# SW6124_A_A_B_C_Lighting_MCU_LED.net
KiCad netlist of a schematic drawn in Altium Designer
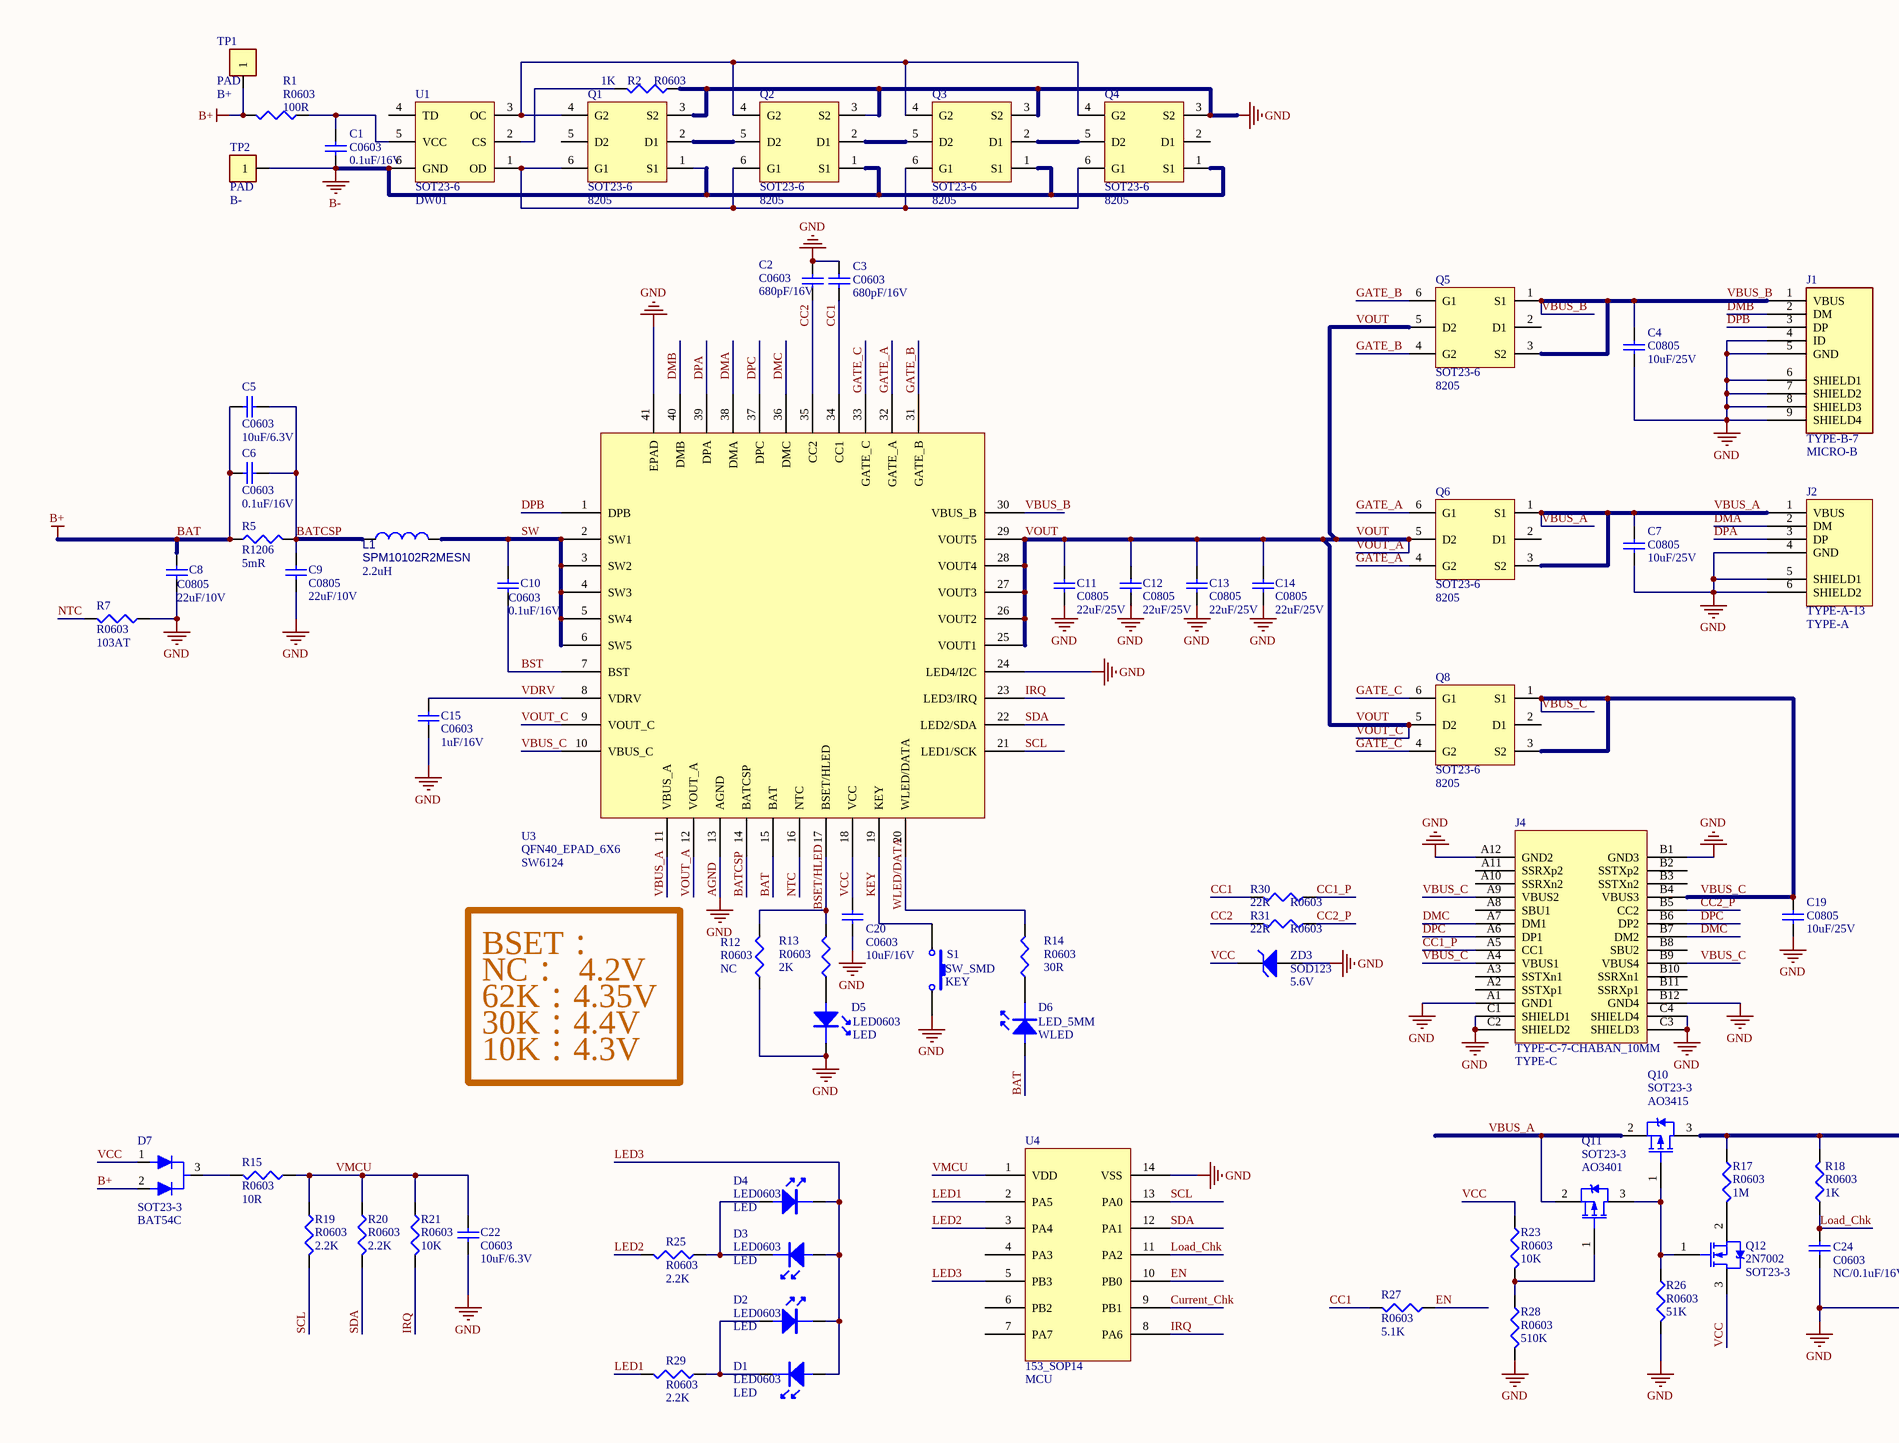
[diagram p0: SW6124+A+A+B+C+Lighting+MCU+LED.SchDoc, left]
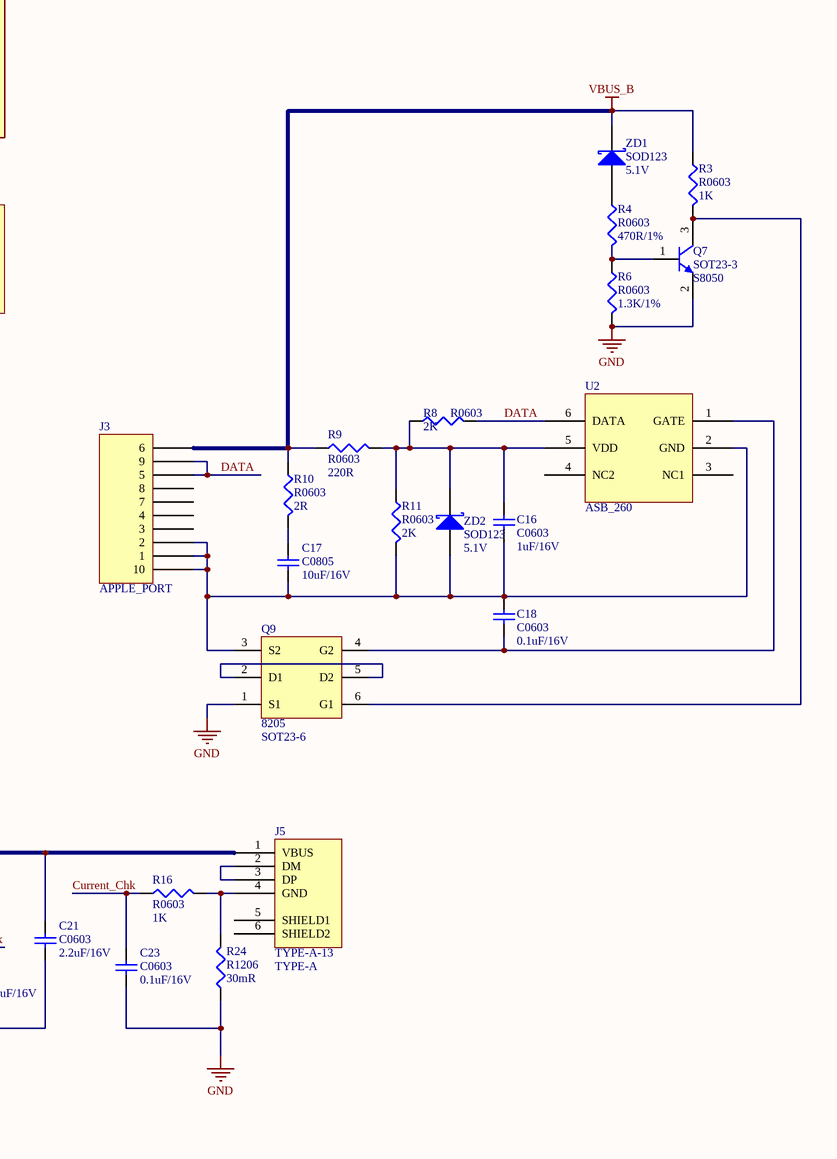
[diagram p1: SW6124+A+A+B+C+Lighting+MCU+LED.SchDoc, right]

(export (version "E")
  (design (tool "Eeschema 10.0.6"))
  (components
    (comp (ref "C1")
      (value "C0603")
      (footprint "C0603")
      (description "Capacitor")
      (fields (field (name "ALTIUM_VALUE") "0.1uF/16V") (field (name "PUBLISHER") "Altium Limited"))
      (libsource (lib "*") (part "Cap"))
    )
    (comp (ref "C2")
      (value "C0603")
      (footprint "C0603")
      (description "Capacitor")
      (fields (field (name "ALTIUM_VALUE") "680pF/16V") (field (name "PUBLISHER") "Altium Limited"))
      (libsource (lib "*") (part "CAP0603"))
    )
    (comp (ref "C3")
      (value "C0603")
      (footprint "C0603")
      (description "Capacitor")
      (fields (field (name "ALTIUM_VALUE") "680pF/16V") (field (name "PUBLISHER") "Altium Limited"))
      (libsource (lib "*") (part "CAP0603"))
    )
    (comp (ref "C4")
      (value "C0805")
      (footprint "C0805")
      (description "Capacitor")
      (fields (field (name "ALTIUM_VALUE") "10uF/25V") (field (name "PUBLISHER") "Altium Limited"))
      (libsource (lib "*") (part "CAP0603"))
    )
    (comp (ref "C5")
      (value "C0603")
      (footprint "C0603")
      (description "Capacitor")
      (fields (field (name "ALTIUM_VALUE") "10uF/6.3V") (field (name "PUBLISHER") "Altium Limited"))
      (libsource (lib "*") (part "CAP0603"))
    )
    (comp (ref "C6")
      (value "C0603")
      (footprint "C0603")
      (description "Capacitor")
      (fields (field (name "ALTIUM_VALUE") "0.1uF/16V") (field (name "PUBLISHER") "Altium Limited"))
      (libsource (lib "*") (part "CAP0603"))
    )
    (comp (ref "C7")
      (value "C0805")
      (footprint "C0805")
      (description "Capacitor")
      (fields (field (name "ALTIUM_VALUE") "10uF/25V") (field (name "PUBLISHER") "Altium Limited"))
      (libsource (lib "*") (part "CAP0603"))
    )
    (comp (ref "C8")
      (value "C0805")
      (footprint "C0805")
      (description "Capacitor")
      (fields (field (name "ALTIUM_VALUE") "22uF/10V") (field (name "PUBLISHER") "Altium Limited"))
      (libsource (lib "*") (part "CAP0805"))
    )
    (comp (ref "C9")
      (value "C0805")
      (footprint "C0805")
      (description "Capacitor")
      (fields (field (name "ALTIUM_VALUE") "22uF/10V") (field (name "PUBLISHER") "Altium Limited"))
      (libsource (lib "*") (part "CAP0805"))
    )
    (comp (ref "C10")
      (value "C0603")
      (footprint "C0603")
      (description "Capacitor")
      (fields (field (name "ALTIUM_VALUE") "0.1uF/16V") (field (name "PUBLISHER") "Altium Limited"))
      (libsource (lib "*") (part "CAP0603"))
    )
    (comp (ref "C11")
      (value "C0805")
      (footprint "C0805")
      (description "Capacitor")
      (fields (field (name "ALTIUM_VALUE") "22uF/25V") (field (name "PUBLISHER") "Altium Limited"))
      (libsource (lib "*") (part "CAP0805"))
    )
    (comp (ref "C12")
      (value "C0805")
      (footprint "C0805")
      (description "Capacitor")
      (fields (field (name "ALTIUM_VALUE") "22uF/25V") (field (name "PUBLISHER") "Altium Limited"))
      (libsource (lib "*") (part "CAP0805"))
    )
    (comp (ref "C13")
      (value "C0805")
      (footprint "C0805")
      (description "Capacitor")
      (fields (field (name "ALTIUM_VALUE") "22uF/25V") (field (name "PUBLISHER") "Altium Limited"))
      (libsource (lib "*") (part "CAP0805"))
    )
    (comp (ref "C14")
      (value "C0805")
      (footprint "C0805")
      (description "Capacitor")
      (fields (field (name "ALTIUM_VALUE") "22uF/25V") (field (name "PUBLISHER") "Altium Limited"))
      (libsource (lib "*") (part "CAP0805"))
    )
    (comp (ref "C15")
      (value "C0603")
      (footprint "C0603")
      (description "Capacitor")
      (fields (field (name "ALTIUM_VALUE") "1uF/16V") (field (name "PUBLISHER") "Altium Limited"))
      (libsource (lib "*") (part "CAP0603"))
    )
    (comp (ref "C16")
      (value "C0603")
      (footprint "C0603")
      (description "Capacitor")
      (fields (field (name "ALTIUM_VALUE") "1uF/16V") (field (name "PUBLISHER") "Altium Limited"))
      (libsource (lib "*") (part "CAP0805"))
    )
    (comp (ref "C17")
      (value "C0805")
      (footprint "C0805")
      (description "Capacitor")
      (fields (field (name "ALTIUM_VALUE") "10uF/16V") (field (name "PUBLISHER") "Altium Limited"))
      (libsource (lib "*") (part "CAP0805"))
    )
    (comp (ref "C18")
      (value "C0603")
      (footprint "C0603")
      (description "Capacitor")
      (fields (field (name "ALTIUM_VALUE") "0.1uF/16V") (field (name "PUBLISHER") "Altium Limited"))
      (libsource (lib "*") (part "CAP0805"))
    )
    (comp (ref "C19")
      (value "C0805")
      (footprint "C0805")
      (description "Capacitor")
      (fields (field (name "ALTIUM_VALUE") "10uF/25V") (field (name "PUBLISHER") "Altium Limited"))
      (libsource (lib "*") (part "CAP0603"))
    )
    (comp (ref "C20")
      (value "C0603")
      (footprint "C0603")
      (description "Capacitor")
      (fields (field (name "ALTIUM_VALUE") "10uF/16V") (field (name "PUBLISHER") "Altium Limited"))
      (libsource (lib "*") (part "CAP0603"))
    )
    (comp (ref "C21")
      (value "C0603")
      (footprint "C0603")
      (description "Capacitor")
      (fields (field (name "ALTIUM_VALUE") "2.2uF/16V") (field (name "PUBLISHER") "Altium Limited"))
      (libsource (lib "*") (part "CAP0603"))
    )
    (comp (ref "C22")
      (value "C0603")
      (footprint "C0603")
      (description "Capacitor")
      (fields (field (name "ALTIUM_VALUE") "10uF/6.3V") (field (name "PUBLISHER") "Altium Limited"))
      (libsource (lib "*") (part "CAP0603"))
    )
    (comp (ref "C23")
      (value "C0603")
      (footprint "C0603")
      (description "Capacitor")
      (fields (field (name "ALTIUM_VALUE") "0.1uF/16V") (field (name "PUBLISHER") "Altium Limited"))
      (libsource (lib "*") (part "CAP0603"))
    )
    (comp (ref "C24")
      (value "C0603")
      (footprint "C0603")
      (description "Capacitor")
      (fields (field (name "ALTIUM_VALUE") "NC/0.1uF/16V") (field (name "PUBLISHER") "Altium Limited"))
      (libsource (lib "*") (part "CAP0603"))
    )
    (comp (ref "D1") (value "LED") (footprint "LED0603") (libsource (lib "*") (part "LED")))
    (comp (ref "D2") (value "LED") (footprint "LED0603") (libsource (lib "*") (part "LED")))
    (comp (ref "D3") (value "LED") (footprint "LED0603") (libsource (lib "*") (part "LED")))
    (comp (ref "D4") (value "LED") (footprint "LED0603") (libsource (lib "*") (part "LED")))
    (comp (ref "D5") (value "LED") (footprint "LED0603") (libsource (lib "*") (part "LED")))
    (comp (ref "D6")
      (value "WLED")
      (footprint "LED_5MM")
      (fields (field (name "FOOTPRINF") "LED_5MM") (field (name "Comment") "LED_5MM"))
      (libsource (lib "*") (part "LED"))
    )
    (comp (ref "D7") (value "BAT54C") (footprint "SOT23-3") (libsource (lib "Schlib1-2012") (part "D3")))
    (comp (ref "J1")
      (value "MICRO-B")
      (footprint "TYPE-B-7")
      (fields (field (name "FOOTPRINTF") "TYPE-B-7") (field (name "Comment") "USB_MICRO_B"))
      (libsource (lib "*") (part "USB_MICRO_B"))
    )
    (comp (ref "J2")
      (value "TYPE-A")
      (footprint "TYPE-A-13")
      (fields (field (name "FOOTPRINF") "TYPE-A-13") (field (name "Comment") "TYPE-A-1"))
      (libsource (lib "*") (part "TYPE-A-1"))
    )
    (comp (ref "J3") (value "APPLE_PORT") (libsource (lib "TEST") (part "APPLE_PORT")))
    (comp (ref "J4")
      (value "TYPE-C")
      (footprint "TYPE-C-7-CHABAN_10MM")
      (libsource (lib "*") (part "TYPE-C"))
    )
    (comp (ref "J5")
      (value "TYPE-A")
      (footprint "PIE10-USB")
      (fields (field (name "FOOTPRINF") "TYPE-A-13") (field (name "Comment") "TYPE-A-1"))
      (libsource (lib "*") (part "TYPE-A-1"))
    )
    (comp (ref "L1")
      (value "SPM10102R2MESN")
      (footprint "INDUCTOR_SPM1010")
      (fields (field (name "ALTIUM_VALUE") "2.2uH"))
      (libsource (lib "*") (part "INDUCTOR"))
    )
    (comp (ref "Q1")
      (value "8205")
      (footprint "SOT23-6")
      (fields (field (name "FOOTPRINF") "SOT23-6"))
      (libsource (lib "") (part "8205B_2"))
    )
    (comp (ref "Q2")
      (value "8205")
      (footprint "SOT23-6")
      (fields (field (name "FOOTPRINF") "SOT23-6"))
      (libsource (lib "") (part "8205B_2"))
    )
    (comp (ref "Q3")
      (value "8205")
      (footprint "SOT23-6")
      (fields (field (name "FOOTPRINF") "SOT23-6"))
      (libsource (lib "") (part "8205B_2"))
    )
    (comp (ref "Q4")
      (value "8205")
      (footprint "SOT23-6")
      (fields (field (name "FOOTPRINF") "SOT23-6"))
      (libsource (lib "") (part "8205B_2"))
    )
    (comp (ref "Q5")
      (value "8205")
      (footprint "SOT23-6")
      (fields (field (name "FOOTPRINF") "SOT23-6"))
      (libsource (lib "*") (part "8205B"))
    )
    (comp (ref "Q6")
      (value "8205")
      (footprint "SOT23-6")
      (fields (field (name "FOOTPRINF") "SOT23-6"))
      (libsource (lib "*") (part "8205B"))
    )
    (comp (ref "Q7")
      (value "S8050")
      (footprint "SOT23-3")
      (description "NPN General Purpose Amplifier")
      (fields (field (name "PUBLISHER") "Altium Limited"))
      (libsource (lib "Miscellaneous Devices") (part "2N3904"))
    )
    (comp (ref "Q8")
      (value "8205")
      (footprint "SOT23-6")
      (fields (field (name "FOOTPRINF") "SOT23-6"))
      (libsource (lib "*") (part "8205B"))
    )
    (comp (ref "Q9")
      (value "8205")
      (footprint "SOT23-6")
      (fields (field (name "FOOTPRINF") "SOT23-6"))
      (libsource (lib "") (part "8205B_1"))
    )
    (comp (ref "Q10")
      (value "AO3415")
      (footprint "SOT23-3")
      (description "P-Channel Power MOSFET")
      (fields (field (name "Comment") "PMOS-2") (field (name "PUBLISHER") "Altium Limited"))
      (libsource (lib "Miscellaneous Devices") (part "PMOS-2"))
    )
    (comp (ref "Q11")
      (value "AO3401")
      (footprint "SOT23-3")
      (description "P-Channel Power MOSFET")
      (fields (field (name "Comment") "PMOS-2") (field (name "PUBLISHER") "Altium Limited"))
      (libsource (lib "Miscellaneous Devices") (part "PMOS-2"))
    )
    (comp (ref "Q12")
      (value "2N7002")
      (footprint "SOT23-3")
      (description "N-Channel Power MOSFET")
      (fields (field (name "Comment") "NMOS-2") (field (name "PUBLISHER") "Altium Limited"))
      (libsource (lib "Miscellaneous Devices") (part "NMOS-2"))
    )
    (comp (ref "R1")
      (value "R0603")
      (footprint "R0603")
      (description "Resistor")
      (fields (field (name "ALTIUM_VALUE") "100R") (field (name "PUBLISHER") "Altium Limited"))
      (libsource (lib "*") (part "Res3"))
    )
    (comp (ref "R2")
      (value "R0603")
      (footprint "R0603")
      (description "Resistor")
      (fields (field (name "ALTIUM_VALUE") "1K") (field (name "PUBLISHER") "Altium Limited"))
      (libsource (lib "*") (part "Res3"))
    )
    (comp (ref "R3")
      (value "R0603")
      (footprint "R0603")
      (description "Resistor")
      (fields (field (name "ALTIUM_VALUE") "1K") (field (name "PUBLISHER") "Altium Limited"))
      (libsource (lib "Miscellaneous Devices") (part "Res3"))
    )
    (comp (ref "R4")
      (value "R0603")
      (footprint "R0603")
      (description "Resistor")
      (fields (field (name "ALTIUM_VALUE") "470R/1%") (field (name "PUBLISHER") "Altium Limited"))
      (libsource (lib "Miscellaneous Devices") (part "Res3"))
    )
    (comp (ref "R5")
      (value "R1206")
      (footprint "R1206")
      (description "Resistor")
      (fields (field (name "ALTIUM_VALUE") "5mR") (field (name "PUBLISHER") "Altium Limited"))
      (libsource (lib "*") (part "RES"))
    )
    (comp (ref "R6")
      (value "R0603")
      (footprint "R0603")
      (description "Resistor")
      (fields (field (name "ALTIUM_VALUE") "1.3K/1%") (field (name "PUBLISHER") "Altium Limited"))
      (libsource (lib "Miscellaneous Devices") (part "Res3"))
    )
    (comp (ref "R7")
      (value "R0603")
      (footprint "R0603")
      (description "Resistor")
      (fields (field (name "ALTIUM_VALUE") "103AT") (field (name "PUBLISHER") "Altium Limited"))
      (libsource (lib "*") (part "RES"))
    )
    (comp (ref "R8")
      (value "R0603")
      (footprint "R0603")
      (description "Resistor")
      (fields (field (name "ALTIUM_VALUE") "2K") (field (name "PUBLISHER") "Altium Limited"))
      (libsource (lib "Miscellaneous Devices") (part "Res3"))
    )
    (comp (ref "R9")
      (value "R0603")
      (footprint "R0603")
      (description "Resistor")
      (fields (field (name "ALTIUM_VALUE") "220R") (field (name "PUBLISHER") "Altium Limited"))
      (libsource (lib "Miscellaneous Devices") (part "Res3"))
    )
    (comp (ref "R10")
      (value "R0603")
      (footprint "R0603")
      (description "Resistor")
      (fields (field (name "ALTIUM_VALUE") "2R") (field (name "PUBLISHER") "Altium Limited"))
      (libsource (lib "Miscellaneous Devices") (part "Res3"))
    )
    (comp (ref "R11")
      (value "R0603")
      (footprint "R0603")
      (description "Resistor")
      (fields (field (name "ALTIUM_VALUE") "2K") (field (name "PUBLISHER") "Altium Limited"))
      (libsource (lib "Miscellaneous Devices") (part "Res3"))
    )
    (comp (ref "R12")
      (value "R0603")
      (footprint "R0603")
      (description "Resistor")
      (fields (field (name "ALTIUM_VALUE") "NC") (field (name "PUBLISHER") "Altium Limited"))
      (libsource (lib "*") (part "RES"))
    )
    (comp (ref "R13")
      (value "R0603")
      (footprint "R0603")
      (description "Resistor")
      (fields (field (name "ALTIUM_VALUE") "2K") (field (name "PUBLISHER") "Altium Limited"))
      (libsource (lib "*") (part "RES"))
    )
    (comp (ref "R14")
      (value "R0603")
      (footprint "R0603")
      (description "Resistor")
      (fields (field (name "ALTIUM_VALUE") "30R") (field (name "PUBLISHER") "Altium Limited"))
      (libsource (lib "*") (part "RES"))
    )
    (comp (ref "R15")
      (value "R0603")
      (footprint "R0603")
      (description "Resistor")
      (fields (field (name "ALTIUM_VALUE") "10R") (field (name "PUBLISHER") "Altium Limited"))
      (libsource (lib "*") (part "RES"))
    )
    (comp (ref "R16")
      (value "R0603")
      (footprint "R0603")
      (description "Resistor")
      (fields (field (name "ALTIUM_VALUE") "1K") (field (name "PUBLISHER") "Altium Limited"))
      (libsource (lib "*") (part "RES"))
    )
    (comp (ref "R17")
      (value "R0603")
      (footprint "R0603")
      (description "Resistor")
      (fields (field (name "ALTIUM_VALUE") "1M") (field (name "PUBLISHER") "Altium Limited"))
      (libsource (lib "*") (part "RES"))
    )
    (comp (ref "R18")
      (value "R0603")
      (footprint "R0603")
      (description "Resistor")
      (fields (field (name "ALTIUM_VALUE") "1K") (field (name "PUBLISHER") "Altium Limited"))
      (libsource (lib "*") (part "RES"))
    )
    (comp (ref "R19")
      (value "R0603")
      (footprint "R0603")
      (description "Resistor")
      (fields (field (name "ALTIUM_VALUE") "2.2K") (field (name "PUBLISHER") "Altium Limited"))
      (libsource (lib "*") (part "RES"))
    )
    (comp (ref "R20")
      (value "R0603")
      (footprint "R0603")
      (description "Resistor")
      (fields (field (name "ALTIUM_VALUE") "2.2K") (field (name "PUBLISHER") "Altium Limited"))
      (libsource (lib "*") (part "RES"))
    )
    (comp (ref "R21")
      (value "R0603")
      (footprint "R0603")
      (description "Resistor")
      (fields (field (name "ALTIUM_VALUE") "10K") (field (name "PUBLISHER") "Altium Limited"))
      (libsource (lib "*") (part "RES"))
    )
    (comp (ref "R23")
      (value "R0603")
      (footprint "R0603")
      (description "Resistor")
      (fields (field (name "ALTIUM_VALUE") "10K") (field (name "PUBLISHER") "Altium Limited"))
      (libsource (lib "*") (part "RES"))
    )
    (comp (ref "R24")
      (value "R1206")
      (footprint "C-1206A")
      (description "Resistor")
      (fields (field (name "ALTIUM_VALUE") "30mR") (field (name "PUBLISHER") "Altium Limited"))
      (libsource (lib "*") (part "RES"))
    )
    (comp (ref "R25")
      (value "R0603")
      (footprint "R0603")
      (description "Resistor")
      (fields (field (name "ALTIUM_VALUE") "2.2K") (field (name "PUBLISHER") "Altium Limited"))
      (libsource (lib "*") (part "RES"))
    )
    (comp (ref "R26")
      (value "R0603")
      (footprint "R0603")
      (description "Resistor")
      (fields (field (name "ALTIUM_VALUE") "51K") (field (name "PUBLISHER") "Altium Limited"))
      (libsource (lib "*") (part "RES"))
    )
    (comp (ref "R27")
      (value "R0603")
      (footprint "R0603")
      (description "Resistor")
      (fields (field (name "ALTIUM_VALUE") "5.1K") (field (name "PUBLISHER") "Altium Limited"))
      (libsource (lib "*") (part "RES"))
    )
    (comp (ref "R28")
      (value "R0603")
      (footprint "R0603")
      (description "Resistor")
      (fields (field (name "ALTIUM_VALUE") "510K") (field (name "PUBLISHER") "Altium Limited"))
      (libsource (lib "*") (part "RES"))
    )
    (comp (ref "R29")
      (value "R0603")
      (footprint "R0603")
      (description "Resistor")
      (fields (field (name "ALTIUM_VALUE") "2.2K") (field (name "PUBLISHER") "Altium Limited"))
      (libsource (lib "*") (part "RES"))
    )
    (comp (ref "R30")
      (value "R0603")
      (footprint "R0603")
      (description "Resistor")
      (fields (field (name "ALTIUM_VALUE") "22R") (field (name "PUBLISHER") "Altium Limited"))
      (libsource (lib "*") (part "RES"))
    )
    (comp (ref "R31")
      (value "R0603")
      (footprint "R0603")
      (description "Resistor")
      (fields (field (name "ALTIUM_VALUE") "22R") (field (name "PUBLISHER") "Altium Limited"))
      (libsource (lib "*") (part "RES"))
    )
    (comp (ref "S1")
      (value "KEY")
      (footprint "SW_SMD")
      (fields (field (name "FOOTPRINF") "SW_SMD"))
      (libsource (lib "*") (part "SW K"))
    )
    (comp (ref "TP1") (value "B+") (footprint "PAD") (libsource (lib "*") (part "Test Point")))
    (comp (ref "TP2") (value "B-") (footprint "PAD") (libsource (lib "") (part "Test Point_1")))
    (comp (ref "U1")
      (value "DW01")
      (footprint "SOT23-6")
      (fields (field (name "FOOTPRINF") "SOT23-6"))
      (libsource (lib "*") (part "DW01"))
    )
    (comp (ref "U2") (value "ASB_260") (footprint "SOT-23-") (libsource (lib "TEST") (part "ASB_260")))
    (comp (ref "U3")
      (value "SW6124")
      (footprint "QFN40_EPAD_6X6")
      (libsource (lib "TEST") (part "SW6106_AFC"))
    )
    (comp (ref "U4")
      (value "153_SOP14")
      (fields (field (name "ALTIUM_VALUE") "MCU"))
      (libsource (lib "TEST") (part "153_SOP14"))
    )
    (comp (ref "ZD1")
      (value "5.1V")
      (footprint "SOD123")
      (description "Schottky Rectifier")
      (fields (field (name "Comment") "SOD123") (field (name "PUBLISHER") "Altium Limited"))
      (libsource (lib "Miscellaneous Devices") (part "Diode 11DQ03"))
    )
    (comp (ref "ZD2")
      (value "5.1V")
      (footprint "SOD123")
      (description "Schottky Rectifier")
      (fields (field (name "Comment") "SOD123") (field (name "PUBLISHER") "Altium Limited"))
      (libsource (lib "Miscellaneous Devices") (part "Diode 11DQ03"))
    )
    (comp (ref "ZD3")
      (value "SOD123")
      (footprint "SOD-123")
      (description "Zener Diode")
      (fields (field (name "ALTIUM_VALUE") "5.6V"))
      (libsource (lib "Miscellaneous Devices") (part "D Zener"))
    )
  )
  (nets
    (net (code "1") (name "/BATCSP") (class "Default")
      (node (ref "C5") (pin "2") (pinfunction "2_2") (pintype "passive"))
      (node (ref "C6") (pin "2") (pinfunction "2_2") (pintype "passive"))
      (node (ref "C9") (pin "2") (pinfunction "2_2") (pintype "passive"))
      (node (ref "L1") (pin "1") (pinfunction "1_1") (pintype "passive"))
      (node (ref "R5") (pin "2") (pinfunction "2_2") (pintype "passive"))
      (node (ref "U3") (pin "14") (pinfunction "BATCSP_14") (pintype "passive"))
    )
    (net (code "2") (name "/BSET{slash}HLED") (class "Default")
      (node (ref "R12") (pin "2") (pinfunction "2_2") (pintype "passive"))
      (node (ref "R13") (pin "2") (pinfunction "2_2") (pintype "passive"))
      (node (ref "U3") (pin "17") (pinfunction "BSET/HLED_17") (pintype "passive"))
    )
    (net (code "3") (name "/BST") (class "Default")
      (node (ref "C10") (pin "1") (pinfunction "1_1") (pintype "passive"))
      (node (ref "U3") (pin "7") (pinfunction "BST_7") (pintype "passive"))
    )
    (net (code "4") (name "/CC1") (class "Default")
      (node (ref "C3") (pin "1") (pinfunction "1_1") (pintype "passive"))
      (node (ref "R27") (pin "2") (pinfunction "2_2") (pintype "passive"))
      (node (ref "R30") (pin "2") (pinfunction "2_2") (pintype "passive"))
      (node (ref "U3") (pin "34") (pinfunction "CC1_34") (pintype "passive"))
    )
    (net (code "5") (name "/CC1_P") (class "Default")
      (node (ref "J4") (pin "A5") (pinfunction "CC1_A5") (pintype "passive"))
      (node (ref "R30") (pin "1") (pinfunction "1_1") (pintype "passive"))
    )
    (net (code "6") (name "/CC2") (class "Default")
      (node (ref "C2") (pin "1") (pinfunction "1_1") (pintype "passive"))
      (node (ref "R31") (pin "2") (pinfunction "2_2") (pintype "passive"))
      (node (ref "U3") (pin "35") (pinfunction "CC2_35") (pintype "passive"))
    )
    (net (code "7") (name "/CC2_P") (class "Default")
      (node (ref "J4") (pin "B5") (pinfunction "CC2_B5") (pintype "passive"))
      (node (ref "R31") (pin "1") (pinfunction "1_1") (pintype "passive"))
    )
    (net (code "8") (name "/Current_Chk") (class "Default")
      (node (ref "C23") (pin "2") (pinfunction "2_2") (pintype "passive"))
      (node (ref "R16") (pin "1") (pinfunction "1_1") (pintype "passive"))
      (node (ref "U4") (pin "9") (pinfunction "PB1_9") (pintype "passive"))
    )
    (net (code "9") (name "/DATA") (class "Default")
      (node (ref "J3") (pin "5") (pinfunction "5_5") (pintype "passive"))
      (node (ref "J3") (pin "9") (pinfunction "9_9") (pintype "passive"))
      (node (ref "R8") (pin "2") (pinfunction "2_2") (pintype "passive"))
      (node (ref "U2") (pin "6") (pinfunction "DATA_6") (pintype "passive"))
    )
    (net (code "10") (name "/DMA") (class "Default")
      (node (ref "J2") (pin "2") (pinfunction "DM_2") (pintype "passive"))
      (node (ref "U3") (pin "38") (pinfunction "DMA_38") (pintype "passive"))
    )
    (net (code "11") (name "/DMB") (class "Default")
      (node (ref "J1") (pin "2") (pinfunction "DM_2") (pintype "passive"))
      (node (ref "U3") (pin "40") (pinfunction "DMB_40") (pintype "passive"))
    )
    (net (code "12") (name "/DMC") (class "Default")
      (node (ref "J4") (pin "A7") (pinfunction "DM1_A7") (pintype "passive"))
      (node (ref "J4") (pin "B7") (pinfunction "DM2_B7") (pintype "passive"))
      (node (ref "U3") (pin "36") (pinfunction "DMC_36") (pintype "passive"))
    )
    (net (code "13") (name "/DPA") (class "Default")
      (node (ref "J2") (pin "3") (pinfunction "DP_3") (pintype "passive"))
      (node (ref "U3") (pin "39") (pinfunction "DPA_39") (pintype "passive"))
    )
    (net (code "14") (name "/DPB") (class "Default")
      (node (ref "J1") (pin "3") (pinfunction "DP_3") (pintype "passive"))
      (node (ref "U3") (pin "1") (pinfunction "DPB_1") (pintype "passive"))
    )
    (net (code "15") (name "/DPC") (class "Default")
      (node (ref "J4") (pin "A6") (pinfunction "DP1_A6") (pintype "passive"))
      (node (ref "J4") (pin "B6") (pinfunction "DP2_B6") (pintype "passive"))
      (node (ref "U3") (pin "37") (pinfunction "DPC_37") (pintype "passive"))
    )
    (net (code "16") (name "/EN") (class "Default")
      (node (ref "R27") (pin "1") (pinfunction "1_1") (pintype "passive"))
      (node (ref "U4") (pin "10") (pinfunction "PB0_10") (pintype "passive"))
    )
    (net (code "17") (name "/GATE_A") (class "Default")
      (node (ref "Q6") (pin "4") (pinfunction "G2_4") (pintype "passive"))
      (node (ref "Q6") (pin "6") (pinfunction "G1_6") (pintype "passive"))
      (node (ref "U3") (pin "32") (pinfunction "GATE_A_32") (pintype "passive"))
    )
    (net (code "18") (name "/GATE_B") (class "Default")
      (node (ref "Q5") (pin "4") (pinfunction "G2_4") (pintype "passive"))
      (node (ref "Q5") (pin "6") (pinfunction "G1_6") (pintype "passive"))
      (node (ref "U3") (pin "31") (pinfunction "GATE_B_31") (pintype "passive"))
    )
    (net (code "19") (name "/GATE_C") (class "Default")
      (node (ref "Q8") (pin "4") (pinfunction "G2_4") (pintype "passive"))
      (node (ref "Q8") (pin "6") (pinfunction "G1_6") (pintype "passive"))
      (node (ref "U3") (pin "33") (pinfunction "GATE_C_33") (pintype "passive"))
    )
    (net (code "20") (name "/IRQ") (class "Default")
      (node (ref "R21") (pin "2") (pinfunction "2_2") (pintype "passive"))
      (node (ref "U3") (pin "23") (pinfunction "LED3/IRQ_23") (pintype "passive"))
      (node (ref "U4") (pin "8") (pinfunction "PA6_8") (pintype "passive"))
    )
    (net (code "21") (name "/KEY") (class "Default")
      (node (ref "S1") (pin "1") (pinfunction "1_1") (pintype "passive"))
      (node (ref "U3") (pin "19") (pinfunction "KEY_19") (pintype "passive"))
    )
    (net (code "22") (name "/LED1") (class "Default")
      (node (ref "R29") (pin "2") (pinfunction "2_2") (pintype "passive"))
      (node (ref "U4") (pin "2") (pinfunction "PA5_2") (pintype "passive"))
    )
    (net (code "23") (name "/LED2") (class "Default")
      (node (ref "R25") (pin "2") (pinfunction "2_2") (pintype "passive"))
      (node (ref "U4") (pin "3") (pinfunction "PA4_3") (pintype "passive"))
    )
    (net (code "24") (name "/LED3") (class "Default")
      (node (ref "D1") (pin "1") (pinfunction "A_1") (pintype "passive"))
      (node (ref "D2") (pin "2") (pinfunction "K_2") (pintype "passive"))
      (node (ref "D3") (pin "1") (pinfunction "A_1") (pintype "passive"))
      (node (ref "D4") (pin "2") (pinfunction "K_2") (pintype "passive"))
      (node (ref "U4") (pin "5") (pinfunction "PB3_5") (pintype "passive"))
    )
    (net (code "25") (name "/Load_Chk") (class "Default")
      (node (ref "C24") (pin "2") (pinfunction "2_2") (pintype "passive"))
      (node (ref "R18") (pin "1") (pinfunction "1_1") (pintype "passive"))
      (node (ref "U4") (pin "11") (pinfunction "PA2_11") (pintype "passive"))
    )
    (net (code "26") (name "/NTC") (class "Default")
      (node (ref "R7") (pin "2") (pinfunction "2_2") (pintype "passive"))
      (node (ref "U3") (pin "16") (pinfunction "NTC_16") (pintype "passive"))
    )
    (net (code "27") (name "/SCL") (class "Default")
      (node (ref "R19") (pin "2") (pinfunction "2_2") (pintype "passive"))
      (node (ref "U3") (pin "21") (pinfunction "LED1/SCK_21") (pintype "passive"))
      (node (ref "U4") (pin "13") (pinfunction "PA0_13") (pintype "passive"))
    )
    (net (code "28") (name "/SDA") (class "Default")
      (node (ref "R20") (pin "2") (pinfunction "2_2") (pintype "passive"))
      (node (ref "U3") (pin "22") (pinfunction "LED2/SDA_22") (pintype "passive"))
      (node (ref "U4") (pin "12") (pinfunction "PA1_12") (pintype "passive"))
    )
    (net (code "29") (name "/SW") (class "Default")
      (node (ref "C10") (pin "2") (pinfunction "2_2") (pintype "passive"))
      (node (ref "L1") (pin "2") (pinfunction "2_2") (pintype "passive"))
      (node (ref "U3") (pin "2") (pinfunction "SW1_2") (pintype "passive"))
      (node (ref "U3") (pin "3") (pinfunction "SW2_3") (pintype "passive"))
      (node (ref "U3") (pin "4") (pinfunction "SW3_4") (pintype "passive"))
      (node (ref "U3") (pin "5") (pinfunction "SW4_5") (pintype "passive"))
      (node (ref "U3") (pin "6") (pinfunction "SW5_6") (pintype "passive"))
    )
    (net (code "30") (name "/VBUS_A") (class "Default")
      (node (ref "C7") (pin "2") (pinfunction "2_2") (pintype "passive"))
      (node (ref "J2") (pin "1") (pinfunction "VBUS_1") (pintype "passive"))
      (node (ref "Q10") (pin "2") (pinfunction "S_2") (pintype "passive"))
      (node (ref "Q11") (pin "2") (pinfunction "S_2") (pintype "passive"))
      (node (ref "Q6") (pin "1") (pinfunction "S1_1") (pintype "passive"))
      (node (ref "Q6") (pin "3") (pinfunction "S2_3") (pintype "passive"))
      (node (ref "U3") (pin "11") (pinfunction "VBUS_A_11") (pintype "passive"))
    )
    (net (code "31") (name "/VBUS_C") (class "Default")
      (node (ref "C19") (pin "2") (pinfunction "2_2") (pintype "passive"))
      (node (ref "J4") (pin "A4") (pinfunction "VBUS1_A4") (pintype "passive"))
      (node (ref "J4") (pin "A9") (pinfunction "VBUS2_A9") (pintype "passive"))
      (node (ref "J4") (pin "B4") (pinfunction "VBUS3_B4") (pintype "passive"))
      (node (ref "J4") (pin "B9") (pinfunction "VBUS4_B9") (pintype "passive"))
      (node (ref "Q8") (pin "1") (pinfunction "S1_1") (pintype "passive"))
      (node (ref "Q8") (pin "3") (pinfunction "S2_3") (pintype "passive"))
      (node (ref "U3") (pin "10") (pinfunction "VBUS_C_10") (pintype "passive"))
    )
    (net (code "32") (name "/VCC") (class "Default")
      (node (ref "C20") (pin "2") (pinfunction "2_2") (pintype "passive"))
      (node (ref "D7") (pin "1") (pintype "passive"))
      (node (ref "Q12") (pin "3") (pinfunction "D_3") (pintype "passive"))
      (node (ref "R23") (pin "1") (pinfunction "1_1") (pintype "passive"))
      (node (ref "U3") (pin "18") (pinfunction "VCC_18") (pintype "passive"))
      (node (ref "ZD3") (pin "2") (pinfunction "K_2") (pintype "passive"))
    )
    (net (code "33") (name "/VDRV") (class "Default")
      (node (ref "C15") (pin "2") (pinfunction "2_2") (pintype "passive"))
      (node (ref "U3") (pin "8") (pinfunction "VDRV_8") (pintype "passive"))
    )
    (net (code "34") (name "/VMCU") (class "Default")
      (node (ref "C22") (pin "1") (pinfunction "1_1") (pintype "passive"))
      (node (ref "R15") (pin "1") (pinfunction "1_1") (pintype "passive"))
      (node (ref "R19") (pin "1") (pinfunction "1_1") (pintype "passive"))
      (node (ref "R20") (pin "1") (pinfunction "1_1") (pintype "passive"))
      (node (ref "R21") (pin "1") (pinfunction "1_1") (pintype "passive"))
      (node (ref "U4") (pin "1") (pinfunction "VDD_1") (pintype "passive"))
    )
    (net (code "35") (name "/VOUT") (class "Default")
      (node (ref "C11") (pin "2") (pinfunction "2_2") (pintype "passive"))
      (node (ref "C12") (pin "2") (pinfunction "2_2") (pintype "passive"))
      (node (ref "C13") (pin "2") (pinfunction "2_2") (pintype "passive"))
      (node (ref "C14") (pin "2") (pinfunction "2_2") (pintype "passive"))
      (node (ref "Q5") (pin "5") (pinfunction "D2_5") (pintype "passive"))
      (node (ref "Q6") (pin "5") (pinfunction "D2_5") (pintype "passive"))
      (node (ref "Q8") (pin "5") (pinfunction "D2_5") (pintype "passive"))
      (node (ref "U3") (pin "12") (pinfunction "VOUT_A_12") (pintype "passive"))
      (node (ref "U3") (pin "25") (pinfunction "VOUT1_25") (pintype "passive"))
      (node (ref "U3") (pin "26") (pinfunction "VOUT2_26") (pintype "passive"))
      (node (ref "U3") (pin "27") (pinfunction "VOUT3_27") (pintype "passive"))
      (node (ref "U3") (pin "28") (pinfunction "VOUT4_28") (pintype "passive"))
      (node (ref "U3") (pin "29") (pinfunction "VOUT5_29") (pintype "passive"))
      (node (ref "U3") (pin "9") (pinfunction "VOUT_C_9") (pintype "passive"))
    )
    (net (code "36") (name "/WLED{slash}DATA") (class "Default")
      (node (ref "R14") (pin "2") (pinfunction "2_2") (pintype "passive"))
      (node (ref "U3") (pin "20") (pinfunction "WLED/DATA_20") (pintype "passive"))
    )
    (net (code "37") (name "B+") (class "Default")
      (node (ref "C5") (pin "1") (pinfunction "1_1") (pintype "passive"))
      (node (ref "C6") (pin "1") (pinfunction "1_1") (pintype "passive"))
      (node (ref "C8") (pin "2") (pinfunction "2_2") (pintype "passive"))
      (node (ref "D6") (pin "1") (pinfunction "A_1") (pintype "passive"))
      (node (ref "D7") (pin "2") (pintype "passive"))
      (node (ref "R1") (pin "2") (pinfunction "2_2") (pintype "passive"))
      (node (ref "R5") (pin "1") (pinfunction "1_1") (pintype "passive"))
      (node (ref "TP1") (pin "1") (pinfunction "1_1") (pintype "passive"))
      (node (ref "U3") (pin "15") (pinfunction "BAT_15") (pintype "passive"))
    )
    (net (code "38") (name "B-") (class "Default")
      (node (ref "C1") (pin "1") (pinfunction "1_1") (pintype "passive"))
      (node (ref "Q1") (pin "1") (pinfunction "S1_1") (pintype "passive"))
      (node (ref "Q2") (pin "1") (pinfunction "S1_1") (pintype "passive"))
      (node (ref "Q3") (pin "1") (pinfunction "S1_1") (pintype "passive"))
      (node (ref "Q4") (pin "1") (pinfunction "S1_1") (pintype "passive"))
      (node (ref "TP2") (pin "1") (pinfunction "1_1") (pintype "passive"))
      (node (ref "U1") (pin "6") (pinfunction "GND_6") (pintype "passive"))
    )
    (net (code "39") (name "GND") (class "Default")
      (node (ref "C11") (pin "1") (pinfunction "1_1") (pintype "passive"))
      (node (ref "C12") (pin "1") (pinfunction "1_1") (pintype "passive"))
      (node (ref "C13") (pin "1") (pinfunction "1_1") (pintype "passive"))
      (node (ref "C14") (pin "1") (pinfunction "1_1") (pintype "passive"))
      (node (ref "C15") (pin "1") (pinfunction "1_1") (pintype "passive"))
      (node (ref "C19") (pin "1") (pinfunction "1_1") (pintype "passive"))
      (node (ref "C2") (pin "2") (pinfunction "2_2") (pintype "passive"))
      (node (ref "C20") (pin "1") (pinfunction "1_1") (pintype "passive"))
      (node (ref "C21") (pin "1") (pinfunction "1_1") (pintype "passive"))
      (node (ref "C22") (pin "2") (pinfunction "2_2") (pintype "passive"))
      (node (ref "C23") (pin "1") (pinfunction "1_1") (pintype "passive"))
      (node (ref "C24") (pin "1") (pinfunction "1_1") (pintype "passive"))
      (node (ref "C3") (pin "2") (pinfunction "2_2") (pintype "passive"))
      (node (ref "C4") (pin "1") (pinfunction "1_1") (pintype "passive"))
      (node (ref "C7") (pin "1") (pinfunction "1_1") (pintype "passive"))
      (node (ref "C8") (pin "1") (pinfunction "1_1") (pintype "passive"))
      (node (ref "C9") (pin "1") (pinfunction "1_1") (pintype "passive"))
      (node (ref "D5") (pin "2") (pinfunction "K_2") (pintype "passive"))
      (node (ref "J1") (pin "4") (pinfunction "ID_4") (pintype "passive"))
      (node (ref "J1") (pin "5") (pinfunction "GND_5") (pintype "passive"))
      (node (ref "J1") (pin "6") (pinfunction "SHIELD1_6") (pintype "passive"))
      (node (ref "J1") (pin "7") (pinfunction "SHIELD2_7") (pintype "passive"))
      (node (ref "J1") (pin "8") (pinfunction "SHIELD3_8") (pintype "passive"))
      (node (ref "J1") (pin "9") (pinfunction "SHIELD4_9") (pintype "passive"))
      (node (ref "J2") (pin "4") (pinfunction "GND_4") (pintype "passive"))
      (node (ref "J2") (pin "5") (pinfunction "SHIELD1_5") (pintype "passive"))
      (node (ref "J2") (pin "6") (pinfunction "SHIELD2_6") (pintype "passive"))
      (node (ref "J4") (pin "A1") (pinfunction "GND1_A1") (pintype "passive"))
      (node (ref "J4") (pin "A12") (pinfunction "GND2_A12") (pintype "passive"))
      (node (ref "J4") (pin "B1") (pinfunction "GND3_B1") (pintype "passive"))
      (node (ref "J4") (pin "B12") (pinfunction "GND4_B12") (pintype "passive"))
      (node (ref "J4") (pin "C1") (pinfunction "SHIELD1_C1") (pintype "passive"))
      (node (ref "J4") (pin "C2") (pinfunction "SHIELD2_C2") (pintype "passive"))
      (node (ref "J4") (pin "C3") (pinfunction "SHIELD3_C3") (pintype "passive"))
      (node (ref "J4") (pin "C4") (pinfunction "SHIELD4_C4") (pintype "passive"))
      (node (ref "Q1") (pin "3") (pinfunction "S2_3") (pintype "passive"))
      (node (ref "Q2") (pin "3") (pinfunction "S2_3") (pintype "passive"))
      (node (ref "Q3") (pin "3") (pinfunction "S2_3") (pintype "passive"))
      (node (ref "Q4") (pin "3") (pinfunction "S2_3") (pintype "passive"))
      (node (ref "Q7") (pin "2") (pinfunction "E_2") (pintype "passive"))
      (node (ref "Q9") (pin "1") (pinfunction "S1_1") (pintype "passive"))
      (node (ref "R12") (pin "1") (pinfunction "1_1") (pintype "passive"))
      (node (ref "R2") (pin "1") (pinfunction "1_1") (pintype "passive"))
      (node (ref "R24") (pin "1") (pinfunction "1_1") (pintype "passive"))
      (node (ref "R26") (pin "2") (pinfunction "2_2") (pintype "passive"))
      (node (ref "R28") (pin "2") (pinfunction "2_2") (pintype "passive"))
      (node (ref "R6") (pin "2") (pinfunction "2_2") (pintype "passive"))
      (node (ref "R7") (pin "1") (pinfunction "1_1") (pintype "passive"))
      (node (ref "S1") (pin "2") (pinfunction "2_2") (pintype "passive"))
      (node (ref "U3") (pin "13") (pinfunction "AGND_13") (pintype "passive"))
      (node (ref "U3") (pin "24") (pinfunction "LED4/I2C_24") (pintype "passive"))
      (node (ref "U3") (pin "41") (pinfunction "EPAD_41") (pintype "passive"))
      (node (ref "U4") (pin "14") (pinfunction "VSS_14") (pintype "passive"))
      (node (ref "ZD3") (pin "1") (pinfunction "A_1") (pintype "passive"))
    )
    (net (code "40") (name "Net-(C17-Pad2)") (class "Default")
      (node (ref "C17") (pin "2") (pinfunction "2_2") (pintype "passive"))
      (node (ref "R10") (pin "2") (pinfunction "2_2") (pintype "passive"))
    )
    (net (code "41") (name "Net-(D1-K)") (class "Default")
      (node (ref "D1") (pin "2") (pinfunction "K_2") (pintype "passive"))
      (node (ref "D2") (pin "1") (pinfunction "A_1") (pintype "passive"))
      (node (ref "R29") (pin "1") (pinfunction "1_1") (pintype "passive"))
    )
    (net (code "42") (name "Net-(D3-K)") (class "Default")
      (node (ref "D3") (pin "2") (pinfunction "K_2") (pintype "passive"))
      (node (ref "D4") (pin "1") (pinfunction "A_1") (pintype "passive"))
      (node (ref "R25") (pin "1") (pinfunction "1_1") (pintype "passive"))
    )
    (net (code "43") (name "Net-(D5-A)") (class "Default")
      (node (ref "D5") (pin "1") (pinfunction "A_1") (pintype "passive"))
      (node (ref "R13") (pin "1") (pinfunction "1_1") (pintype "passive"))
    )
    (net (code "44") (name "Net-(D6-K)") (class "Default")
      (node (ref "D6") (pin "2") (pinfunction "K_2") (pintype "passive"))
      (node (ref "R14") (pin "1") (pinfunction "1_1") (pintype "passive"))
    )
    (net (code "45") (name "Net-(D7-Pad3)") (class "Default")
      (node (ref "D7") (pin "3") (pintype "passive"))
      (node (ref "R15") (pin "2") (pinfunction "2_2") (pintype "passive"))
    )
    (net (code "46") (name "Net-(J5-DM)") (class "Default")
      (node (ref "J5") (pin "2") (pinfunction "DM_2") (pintype "passive"))
      (node (ref "J5") (pin "3") (pinfunction "DP_3") (pintype "passive"))
    )
    (net (code "47") (name "Net-(J5-GND)") (class "Default")
      (node (ref "J5") (pin "4") (pinfunction "GND_4") (pintype "passive"))
      (node (ref "R16") (pin "2") (pinfunction "2_2") (pintype "passive"))
      (node (ref "R24") (pin "2") (pinfunction "2_2") (pintype "passive"))
    )
    (net (code "48") (name "Net-(J5-VBUS)") (class "Default")
      (node (ref "C21") (pin "2") (pinfunction "2_2") (pintype "passive"))
      (node (ref "J5") (pin "1") (pinfunction "VBUS_1") (pintype "passive"))
      (node (ref "Q10") (pin "3") (pinfunction "D_3") (pintype "passive"))
      (node (ref "R17") (pin "1") (pinfunction "1_1") (pintype "passive"))
      (node (ref "R18") (pin "2") (pinfunction "2_2") (pintype "passive"))
    )
    (net (code "49") (name "Net-(Q1-D1)") (class "Default")
      (node (ref "Q1") (pin "2") (pinfunction "D1_2") (pintype "passive"))
      (node (ref "Q2") (pin "5") (pinfunction "D2_5") (pintype "passive"))
    )
    (net (code "50") (name "Net-(Q1-G1)") (class "Default")
      (node (ref "Q1") (pin "6") (pinfunction "G1_6") (pintype "passive"))
      (node (ref "Q2") (pin "6") (pinfunction "G1_6") (pintype "passive"))
      (node (ref "Q3") (pin "6") (pinfunction "G1_6") (pintype "passive"))
      (node (ref "Q4") (pin "6") (pinfunction "G1_6") (pintype "passive"))
      (node (ref "U1") (pin "1") (pinfunction "OD_1") (pintype "passive"))
    )
    (net (code "51") (name "Net-(Q1-G2)") (class "Default")
      (node (ref "Q1") (pin "4") (pinfunction "G2_4") (pintype "passive"))
      (node (ref "Q2") (pin "4") (pinfunction "G2_4") (pintype "passive"))
      (node (ref "Q3") (pin "4") (pinfunction "G2_4") (pintype "passive"))
      (node (ref "Q4") (pin "4") (pinfunction "G2_4") (pintype "passive"))
      (node (ref "U1") (pin "3") (pinfunction "OC_3") (pintype "passive"))
    )
    (net (code "52") (name "Net-(Q2-D1)") (class "Default")
      (node (ref "Q2") (pin "2") (pinfunction "D1_2") (pintype "passive"))
      (node (ref "Q3") (pin "5") (pinfunction "D2_5") (pintype "passive"))
    )
    (net (code "53") (name "Net-(Q3-D1)") (class "Default")
      (node (ref "Q3") (pin "2") (pinfunction "D1_2") (pintype "passive"))
      (node (ref "Q4") (pin "5") (pinfunction "D2_5") (pintype "passive"))
    )
    (net (code "54") (name "Net-(Q7-B)") (class "Default")
      (node (ref "Q7") (pin "1") (pinfunction "B_1") (pintype "passive"))
      (node (ref "R4") (pin "2") (pinfunction "2_2") (pintype "passive"))
      (node (ref "R6") (pin "1") (pinfunction "1_1") (pintype "passive"))
    )
    (net (code "55") (name "Net-(Q7-C)") (class "Default")
      (node (ref "Q7") (pin "3") (pinfunction "C_3") (pintype "passive"))
      (node (ref "Q9") (pin "6") (pinfunction "G1_6") (pintype "passive"))
      (node (ref "R3") (pin "2") (pinfunction "2_2") (pintype "passive"))
    )
    (net (code "56") (name "Net-(Q9-D1)") (class "Default")
      (node (ref "Q9") (pin "2") (pinfunction "D1_2") (pintype "passive"))
      (node (ref "Q9") (pin "5") (pinfunction "D2_5") (pintype "passive"))
    )
    (net (code "57") (name "Net-(Q9-G2)") (class "Default")
      (node (ref "C18") (pin "1") (pinfunction "1_1") (pintype "passive"))
      (node (ref "Q9") (pin "4") (pinfunction "G2_4") (pintype "passive"))
      (node (ref "U2") (pin "1") (pinfunction "GATE_1") (pintype "passive"))
    )
    (net (code "58") (name "Net-(Q9-S2)") (class "Default")
      (node (ref "C16") (pin "1") (pinfunction "1_1") (pintype "passive"))
      (node (ref "C17") (pin "1") (pinfunction "1_1") (pintype "passive"))
      (node (ref "C18") (pin "2") (pinfunction "2_2") (pintype "passive"))
      (node (ref "J3") (pin "1") (pinfunction "1_1") (pintype "passive"))
      (node (ref "J3") (pin "10") (pinfunction "10_10") (pintype "passive"))
      (node (ref "J3") (pin "2") (pinfunction "2_2") (pintype "passive"))
      (node (ref "Q9") (pin "3") (pinfunction "S2_3") (pintype "passive"))
      (node (ref "R11") (pin "2") (pinfunction "2_2") (pintype "passive"))
      (node (ref "U2") (pin "2") (pinfunction "GND_2") (pintype "passive"))
      (node (ref "ZD2") (pin "1") (pinfunction "A_1") (pintype "passive"))
    )
    (net (code "59") (name "Net-(Q10-G)") (class "Default")
      (node (ref "Q10") (pin "1") (pinfunction "G_1") (pintype "passive"))
      (node (ref "Q11") (pin "3") (pinfunction "D_3") (pintype "passive"))
      (node (ref "Q12") (pin "1") (pinfunction "G_1") (pintype "passive"))
      (node (ref "R26") (pin "1") (pinfunction "1_1") (pintype "passive"))
    )
    (net (code "60") (name "Net-(Q11-G)") (class "Default")
      (node (ref "Q11") (pin "1") (pinfunction "G_1") (pintype "passive"))
      (node (ref "R23") (pin "2") (pinfunction "2_2") (pintype "passive"))
      (node (ref "R28") (pin "1") (pinfunction "1_1") (pintype "passive"))
    )
    (net (code "61") (name "Net-(Q12-S)") (class "Default")
      (node (ref "Q12") (pin "2") (pinfunction "S_2") (pintype "passive"))
      (node (ref "R17") (pin "2") (pinfunction "2_2") (pintype "passive"))
    )
    (net (code "62") (name "Net-(U1-CS)") (class "Default")
      (node (ref "R2") (pin "2") (pinfunction "2_2") (pintype "passive"))
      (node (ref "U1") (pin "2") (pinfunction "CS_2") (pintype "passive"))
    )
    (net (code "63") (name "Net-(U1-VCC)") (class "Default")
      (node (ref "C1") (pin "2") (pinfunction "2_2") (pintype "passive"))
      (node (ref "R1") (pin "1") (pinfunction "1_1") (pintype "passive"))
      (node (ref "U1") (pin "5") (pinfunction "VCC_5") (pintype "passive"))
    )
    (net (code "64") (name "Net-(U2-VDD)") (class "Default")
      (node (ref "C16") (pin "2") (pinfunction "2_2") (pintype "passive"))
      (node (ref "R11") (pin "1") (pinfunction "1_1") (pintype "passive"))
      (node (ref "R8") (pin "1") (pinfunction "1_1") (pintype "passive"))
      (node (ref "R9") (pin "2") (pinfunction "2_2") (pintype "passive"))
      (node (ref "U2") (pin "5") (pinfunction "VDD_5") (pintype "passive"))
      (node (ref "ZD2") (pin "2") (pinfunction "K_2") (pintype "passive"))
    )
    (net (code "65") (name "Net-(ZD1-A)") (class "Default")
      (node (ref "R4") (pin "1") (pinfunction "1_1") (pintype "passive"))
      (node (ref "ZD1") (pin "1") (pinfunction "A_1") (pintype "passive"))
    )
    (net (code "66") (name "VBUS_B") (class "Default")
      (node (ref "C4") (pin "2") (pinfunction "2_2") (pintype "passive"))
      (node (ref "J1") (pin "1") (pinfunction "VBUS_1") (pintype "passive"))
      (node (ref "J3") (pin "6") (pinfunction "6_6") (pintype "passive"))
      (node (ref "Q5") (pin "1") (pinfunction "S1_1") (pintype "passive"))
      (node (ref "Q5") (pin "3") (pinfunction "S2_3") (pintype "passive"))
      (node (ref "R10") (pin "1") (pinfunction "1_1") (pintype "passive"))
      (node (ref "R3") (pin "1") (pinfunction "1_1") (pintype "passive"))
      (node (ref "R9") (pin "1") (pinfunction "1_1") (pintype "passive"))
      (node (ref "U3") (pin "30") (pinfunction "VBUS_B_30") (pintype "passive"))
      (node (ref "ZD1") (pin "2") (pinfunction "K_2") (pintype "passive"))
    )
    (net (code "67") (name "unconnected-(J3-Pad3)") (class "Default")
      (node (ref "J3") (pin "3") (pinfunction "3_3") (pintype "passive"))
    )
    (net (code "68") (name "unconnected-(J3-Pad4)") (class "Default")
      (node (ref "J3") (pin "4") (pinfunction "4_4") (pintype "passive"))
    )
    (net (code "69") (name "unconnected-(J3-Pad7)") (class "Default")
      (node (ref "J3") (pin "7") (pinfunction "7_7") (pintype "passive"))
    )
    (net (code "70") (name "unconnected-(J3-Pad8)") (class "Default")
      (node (ref "J3") (pin "8") (pinfunction "8_8") (pintype "passive"))
    )
    (net (code "71") (name "unconnected-(J4-SBU1-PadA8)") (class "Default")
      (node (ref "J4") (pin "A8") (pinfunction "SBU1_A8") (pintype "passive"))
    )
    (net (code "72") (name "unconnected-(J4-SBU2-PadB8)") (class "Default")
      (node (ref "J4") (pin "B8") (pinfunction "SBU2_B8") (pintype "passive"))
    )
    (net (code "73") (name "unconnected-(J4-SSRXn1-PadB10)") (class "Default")
      (node (ref "J4") (pin "B10") (pinfunction "SSRXn1_B10") (pintype "passive"))
    )
    (net (code "74") (name "unconnected-(J4-SSRXn2-PadA10)") (class "Default")
      (node (ref "J4") (pin "A10") (pinfunction "SSRXn2_A10") (pintype "passive"))
    )
    (net (code "75") (name "unconnected-(J4-SSRXp1-PadB11)") (class "Default")
      (node (ref "J4") (pin "B11") (pinfunction "SSRXp1_B11") (pintype "passive"))
    )
    (net (code "76") (name "unconnected-(J4-SSRXp2-PadA11)") (class "Default")
      (node (ref "J4") (pin "A11") (pinfunction "SSRXp2_A11") (pintype "passive"))
    )
    (net (code "77") (name "unconnected-(J4-SSTXn1-PadA3)") (class "Default")
      (node (ref "J4") (pin "A3") (pinfunction "SSTXn1_A3") (pintype "passive"))
    )
    (net (code "78") (name "unconnected-(J4-SSTXn2-PadB3)") (class "Default")
      (node (ref "J4") (pin "B3") (pinfunction "SSTXn2_B3") (pintype "passive"))
    )
    (net (code "79") (name "unconnected-(J4-SSTXp1-PadA2)") (class "Default")
      (node (ref "J4") (pin "A2") (pinfunction "SSTXp1_A2") (pintype "passive"))
    )
    (net (code "80") (name "unconnected-(J4-SSTXp2-PadB2)") (class "Default")
      (node (ref "J4") (pin "B2") (pinfunction "SSTXp2_B2") (pintype "passive"))
    )
    (net (code "81") (name "unconnected-(J5-SHIELD1-Pad5)") (class "Default")
      (node (ref "J5") (pin "5") (pinfunction "SHIELD1_5") (pintype "passive"))
    )
    (net (code "82") (name "unconnected-(J5-SHIELD2-Pad6)") (class "Default")
      (node (ref "J5") (pin "6") (pinfunction "SHIELD2_6") (pintype "passive"))
    )
    (net (code "83") (name "unconnected-(Q1-D2-Pad5)") (class "Default")
      (node (ref "Q1") (pin "5") (pinfunction "D2_5") (pintype "passive"))
    )
    (net (code "84") (name "unconnected-(Q4-D1-Pad2)") (class "Default")
      (node (ref "Q4") (pin "2") (pinfunction "D1_2") (pintype "passive"))
    )
    (net (code "85") (name "unconnected-(Q5-D1-Pad2)") (class "Default")
      (node (ref "Q5") (pin "2") (pinfunction "D1_2") (pintype "passive"))
    )
    (net (code "86") (name "unconnected-(Q6-D1-Pad2)") (class "Default")
      (node (ref "Q6") (pin "2") (pinfunction "D1_2") (pintype "passive"))
    )
    (net (code "87") (name "unconnected-(Q8-D1-Pad2)") (class "Default")
      (node (ref "Q8") (pin "2") (pinfunction "D1_2") (pintype "passive"))
    )
    (net (code "88") (name "unconnected-(U1-TD-Pad4)") (class "Default")
      (node (ref "U1") (pin "4") (pinfunction "TD_4") (pintype "passive"))
    )
    (net (code "89") (name "unconnected-(U2-NC1-Pad3)") (class "Default")
      (node (ref "U2") (pin "3") (pinfunction "NC1_3") (pintype "passive"))
    )
    (net (code "90") (name "unconnected-(U2-NC2-Pad4)") (class "Default")
      (node (ref "U2") (pin "4") (pinfunction "NC2_4") (pintype "passive"))
    )
    (net (code "91") (name "unconnected-(U4-PA3-Pad4)") (class "Default")
      (node (ref "U4") (pin "4") (pinfunction "PA3_4") (pintype "passive"))
    )
    (net (code "92") (name "unconnected-(U4-PA7-Pad7)") (class "Default")
      (node (ref "U4") (pin "7") (pinfunction "PA7_7") (pintype "passive"))
    )
    (net (code "93") (name "unconnected-(U4-PB2-Pad6)") (class "Default")
      (node (ref "U4") (pin "6") (pinfunction "PB2_6") (pintype "passive"))
    )
  )
)
